# schema.net
KiCad netlist of a schematic drawn in EAGLE
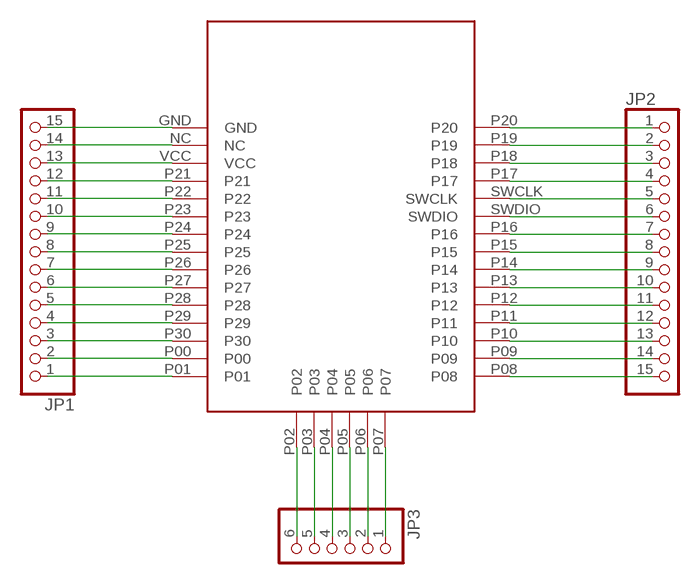
[diagram p0: schematic, sheet 1]

(export (version "E")
  (design (tool "Eeschema 10.0.6"))
  (components
    (comp (ref "JP1")
      (value "PINHD-1X15")
      (footprint "eagle-import:1X15")
      (libsource (lib "eagle-import") (part "PINHD-1X15"))
    )
    (comp (ref "JP2")
      (value "PINHD-1X15")
      (footprint "eagle-import:1X15")
      (libsource (lib "eagle-import") (part "PINHD-1X15"))
    )
    (comp (ref "JP3")
      (value "PINHD-1X6")
      (footprint "eagle-import:1X06")
      (libsource (lib "eagle-import") (part "PINHD-1X6"))
    )
    (comp (ref "U$1")
      (value "XUNTONG")
      (footprint "eagle-import:SMD")
      (libsource (lib "eagle-import") (part "XUNTONG"))
    )
  )
  (nets
    (net (code "1") (name "Net-(JP1-Pad1)") (class "Default")
      (node (ref "JP1") (pin "1") (pinfunction "1_1") (pintype "passive"))
      (node (ref "U$1") (pin "P01") (pinfunction "P01_P01") (pintype "bidirectional"))
    )
    (net (code "2") (name "Net-(JP1-Pad2)") (class "Default")
      (node (ref "JP1") (pin "2") (pinfunction "2_2") (pintype "passive"))
      (node (ref "U$1") (pin "P00") (pinfunction "P00_P00") (pintype "bidirectional"))
    )
    (net (code "3") (name "Net-(JP1-Pad3)") (class "Default")
      (node (ref "JP1") (pin "3") (pinfunction "3_3") (pintype "passive"))
      (node (ref "U$1") (pin "P30") (pinfunction "P30_P30") (pintype "bidirectional"))
    )
    (net (code "4") (name "Net-(JP1-Pad4)") (class "Default")
      (node (ref "JP1") (pin "4") (pinfunction "4_4") (pintype "passive"))
      (node (ref "U$1") (pin "P29") (pinfunction "P29_P29") (pintype "bidirectional"))
    )
    (net (code "5") (name "Net-(JP1-Pad5)") (class "Default")
      (node (ref "JP1") (pin "5") (pinfunction "5_5") (pintype "passive"))
      (node (ref "U$1") (pin "P28") (pinfunction "P28_P28") (pintype "bidirectional"))
    )
    (net (code "6") (name "Net-(JP1-Pad6)") (class "Default")
      (node (ref "JP1") (pin "6") (pinfunction "6_6") (pintype "passive"))
      (node (ref "U$1") (pin "P27") (pinfunction "P27_P27") (pintype "bidirectional"))
    )
    (net (code "7") (name "Net-(JP1-Pad7)") (class "Default")
      (node (ref "JP1") (pin "7") (pinfunction "7_7") (pintype "passive"))
      (node (ref "U$1") (pin "P26") (pinfunction "P26_P26") (pintype "bidirectional"))
    )
    (net (code "8") (name "Net-(JP1-Pad8)") (class "Default")
      (node (ref "JP1") (pin "8") (pinfunction "8_8") (pintype "passive"))
      (node (ref "U$1") (pin "P25") (pinfunction "P25_P25") (pintype "bidirectional"))
    )
    (net (code "9") (name "Net-(JP1-Pad9)") (class "Default")
      (node (ref "JP1") (pin "9") (pinfunction "9_9") (pintype "passive"))
      (node (ref "U$1") (pin "P24") (pinfunction "P24_P24") (pintype "bidirectional"))
    )
    (net (code "10") (name "Net-(JP1-Pad10)") (class "Default")
      (node (ref "JP1") (pin "10") (pinfunction "10_10") (pintype "passive"))
      (node (ref "U$1") (pin "P23") (pinfunction "P23_P23") (pintype "bidirectional"))
    )
    (net (code "11") (name "Net-(JP1-Pad11)") (class "Default")
      (node (ref "JP1") (pin "11") (pinfunction "11_11") (pintype "passive"))
      (node (ref "U$1") (pin "P22") (pinfunction "P22_P22") (pintype "bidirectional"))
    )
    (net (code "12") (name "Net-(JP1-Pad12)") (class "Default")
      (node (ref "JP1") (pin "12") (pinfunction "12_12") (pintype "passive"))
      (node (ref "U$1") (pin "P21") (pinfunction "P21_P21") (pintype "bidirectional"))
    )
    (net (code "13") (name "Net-(JP1-Pad13)") (class "Default")
      (node (ref "JP1") (pin "13") (pinfunction "13_13") (pintype "passive"))
      (node (ref "U$1") (pin "VCC") (pinfunction "VCC_VCC") (pintype "bidirectional"))
    )
    (net (code "14") (name "Net-(JP1-Pad14)") (class "Default")
      (node (ref "JP1") (pin "14") (pinfunction "14_14") (pintype "passive"))
      (node (ref "U$1") (pin "NC") (pinfunction "NC_NC") (pintype "bidirectional"))
    )
    (net (code "15") (name "Net-(JP1-Pad15)") (class "Default")
      (node (ref "JP1") (pin "15") (pinfunction "15_15") (pintype "passive"))
      (node (ref "U$1") (pin "GND") (pinfunction "GND_GND") (pintype "bidirectional"))
    )
    (net (code "16") (name "Net-(JP2-Pad1)") (class "Default")
      (node (ref "JP2") (pin "1") (pinfunction "1_1") (pintype "passive"))
      (node (ref "U$1") (pin "P20") (pinfunction "P20_P20") (pintype "bidirectional"))
    )
    (net (code "17") (name "Net-(JP2-Pad2)") (class "Default")
      (node (ref "JP2") (pin "2") (pinfunction "2_2") (pintype "passive"))
      (node (ref "U$1") (pin "P19") (pinfunction "P19_P19") (pintype "bidirectional"))
    )
    (net (code "18") (name "Net-(JP2-Pad3)") (class "Default")
      (node (ref "JP2") (pin "3") (pinfunction "3_3") (pintype "passive"))
      (node (ref "U$1") (pin "P18") (pinfunction "P18_P18") (pintype "bidirectional"))
    )
    (net (code "19") (name "Net-(JP2-Pad4)") (class "Default")
      (node (ref "JP2") (pin "4") (pinfunction "4_4") (pintype "passive"))
      (node (ref "U$1") (pin "P17") (pinfunction "P17_P17") (pintype "bidirectional"))
    )
    (net (code "20") (name "Net-(JP2-Pad5)") (class "Default")
      (node (ref "JP2") (pin "5") (pinfunction "5_5") (pintype "passive"))
      (node (ref "U$1") (pin "SWCLK") (pinfunction "SWCLK_SWCLK") (pintype "bidirectional"))
    )
    (net (code "21") (name "Net-(JP2-Pad6)") (class "Default")
      (node (ref "JP2") (pin "6") (pinfunction "6_6") (pintype "passive"))
      (node (ref "U$1") (pin "SWDIO") (pinfunction "SWDIO_SWDIO") (pintype "bidirectional"))
    )
    (net (code "22") (name "Net-(JP2-Pad7)") (class "Default")
      (node (ref "JP2") (pin "7") (pinfunction "7_7") (pintype "passive"))
      (node (ref "U$1") (pin "P16") (pinfunction "P16_P16") (pintype "bidirectional"))
    )
    (net (code "23") (name "Net-(JP2-Pad8)") (class "Default")
      (node (ref "JP2") (pin "8") (pinfunction "8_8") (pintype "passive"))
      (node (ref "U$1") (pin "P15") (pinfunction "P15_P15") (pintype "bidirectional"))
    )
    (net (code "24") (name "Net-(JP2-Pad9)") (class "Default")
      (node (ref "JP2") (pin "9") (pinfunction "9_9") (pintype "passive"))
      (node (ref "U$1") (pin "P14") (pinfunction "P14_P14") (pintype "bidirectional"))
    )
    (net (code "25") (name "Net-(JP2-Pad10)") (class "Default")
      (node (ref "JP2") (pin "10") (pinfunction "10_10") (pintype "passive"))
      (node (ref "U$1") (pin "P13") (pinfunction "P13_P13") (pintype "bidirectional"))
    )
    (net (code "26") (name "Net-(JP2-Pad11)") (class "Default")
      (node (ref "JP2") (pin "11") (pinfunction "11_11") (pintype "passive"))
      (node (ref "U$1") (pin "P12") (pinfunction "P12_P12") (pintype "bidirectional"))
    )
    (net (code "27") (name "Net-(JP2-Pad12)") (class "Default")
      (node (ref "JP2") (pin "12") (pinfunction "12_12") (pintype "passive"))
      (node (ref "U$1") (pin "P11") (pinfunction "P11_P11") (pintype "bidirectional"))
    )
    (net (code "28") (name "Net-(JP2-Pad13)") (class "Default")
      (node (ref "JP2") (pin "13") (pinfunction "13_13") (pintype "passive"))
      (node (ref "U$1") (pin "P10") (pinfunction "P10_P10") (pintype "bidirectional"))
    )
    (net (code "29") (name "Net-(JP2-Pad14)") (class "Default")
      (node (ref "JP2") (pin "14") (pinfunction "14_14") (pintype "passive"))
      (node (ref "U$1") (pin "P09") (pinfunction "P09_P09") (pintype "bidirectional"))
    )
    (net (code "30") (name "Net-(JP2-Pad15)") (class "Default")
      (node (ref "JP2") (pin "15") (pinfunction "15_15") (pintype "passive"))
      (node (ref "U$1") (pin "P08") (pinfunction "P08_P08") (pintype "bidirectional"))
    )
    (net (code "31") (name "Net-(JP3-Pad1)") (class "Default")
      (node (ref "JP3") (pin "1") (pinfunction "1_1") (pintype "passive"))
      (node (ref "U$1") (pin "P07") (pinfunction "P07_P07") (pintype "bidirectional"))
    )
    (net (code "32") (name "Net-(JP3-Pad2)") (class "Default")
      (node (ref "JP3") (pin "2") (pinfunction "2_2") (pintype "passive"))
      (node (ref "U$1") (pin "P06") (pinfunction "P06_P06") (pintype "bidirectional"))
    )
    (net (code "33") (name "Net-(JP3-Pad3)") (class "Default")
      (node (ref "JP3") (pin "3") (pinfunction "3_3") (pintype "passive"))
      (node (ref "U$1") (pin "P05") (pinfunction "P05_P05") (pintype "bidirectional"))
    )
    (net (code "34") (name "Net-(JP3-Pad4)") (class "Default")
      (node (ref "JP3") (pin "4") (pinfunction "4_4") (pintype "passive"))
      (node (ref "U$1") (pin "P04") (pinfunction "P04_P04") (pintype "bidirectional"))
    )
    (net (code "35") (name "Net-(JP3-Pad5)") (class "Default")
      (node (ref "JP3") (pin "5") (pinfunction "5_5") (pintype "passive"))
      (node (ref "U$1") (pin "P03") (pinfunction "P03_P03") (pintype "bidirectional"))
    )
    (net (code "36") (name "Net-(JP3-Pad6)") (class "Default")
      (node (ref "JP3") (pin "6") (pinfunction "6_6") (pintype "passive"))
      (node (ref "U$1") (pin "P02") (pinfunction "P02_P02") (pintype "bidirectional"))
    )
  )
)
